# FTPSC.net
KiCad netlist of a schematic drawn in EAGLE
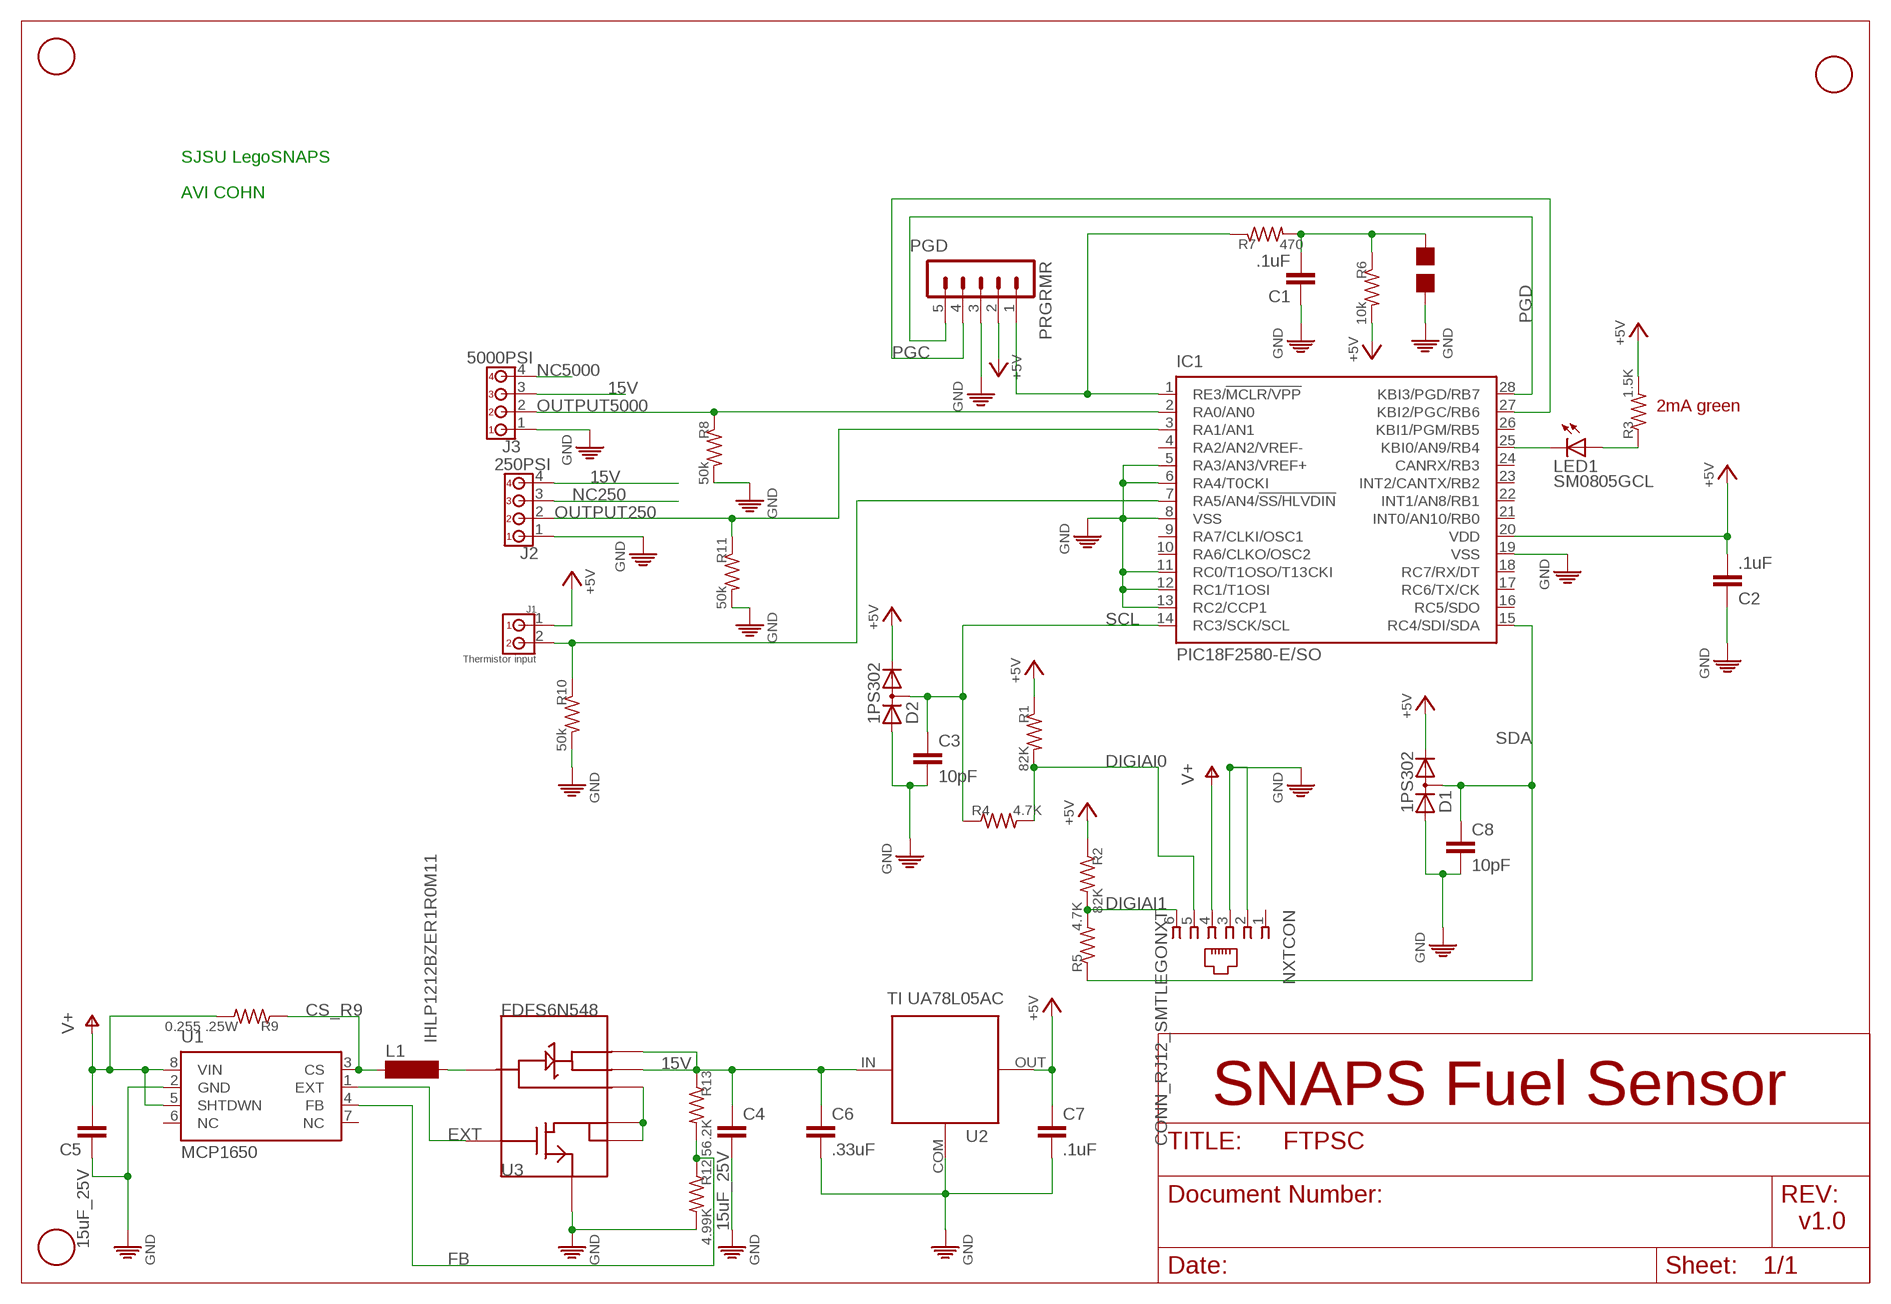
[diagram p0: schematic, sheet 1]

(export (version "E")
  (design (tool "Eeschema 10.0.6"))
  (components
    (comp (ref "C1")
      (value ".1uF")
      (footprint "eagle-import:RCL_C0805")
      (libsource (lib "eagle-import") (part "PASSIVE_CAP_NON-POLC0805"))
    )
    (comp (ref "C2")
      (value ".1uF")
      (footprint "eagle-import:RCL_C0805")
      (libsource (lib "eagle-import") (part "PASSIVE_CAP_NON-POLC0805"))
    )
    (comp (ref "C3")
      (value "10pF")
      (footprint "eagle-import:RCL_C0805")
      (libsource (lib "eagle-import") (part "PASSIVE_CAP_NON-POLC0805"))
    )
    (comp (ref "C4")
      (value "15uF_25V")
      (footprint "eagle-import:RCL_C0805")
      (libsource (lib "eagle-import") (part "PASSIVE_CAP_NON-POLC0805"))
    )
    (comp (ref "C5")
      (value "15uF_25V")
      (footprint "eagle-import:RCL_C0805")
      (libsource (lib "eagle-import") (part "PASSIVE_CAP_NON-POLC0805"))
    )
    (comp (ref "C6")
      (value ".33uF")
      (footprint "eagle-import:RCL_C0805")
      (libsource (lib "eagle-import") (part "PASSIVE_CAP_NON-POLC0805"))
    )
    (comp (ref "C7")
      (value ".1uF")
      (footprint "eagle-import:RCL_C0805")
      (libsource (lib "eagle-import") (part "PASSIVE_CAP_NON-POLC0805"))
    )
    (comp (ref "C8")
      (value "10pF")
      (footprint "eagle-import:RCL_C0805")
      (libsource (lib "eagle-import") (part "PASSIVE_CAP_NON-POLC0805"))
    )
    (comp (ref "D1")
      (value "1PS302")
      (footprint "eagle-import:SC70-3-R")
      (libsource (lib "eagle-import") (part "DIOD_DBL_SERIESSOT323"))
    )
    (comp (ref "D2")
      (value "1PS302")
      (footprint "eagle-import:SC70-3-R")
      (libsource (lib "eagle-import") (part "DIOD_DBL_SERIESSOT323"))
    )
    (comp (ref "IC1")
      (value "PIC18F2580-E/SO")
      (footprint "eagle-import:SO28W")
      (fields (field (name "MF") "MICROCHIP") (field (name "MPN") "PIC18F2580-I/SO"))
      (libsource (lib "eagle-import") (part "PIC18F280-E/SO5"))
    )
    (comp (ref "J1")
      (value "Thermistor input")
      (footprint "eagle-import:CON-MOLEX_22-23-2021")
      (libsource (lib "eagle-import") (part "CONN_KK_2-PIN"))
    )
    (comp (ref "J2")
      (value "250PSI")
      (footprint "eagle-import:CON-MOLEX_22-23-2041")
      (libsource (lib "eagle-import") (part "CONN_KK_4-PIN"))
    )
    (comp (ref "J3")
      (value "5000PSI")
      (footprint "eagle-import:CON-MOLEX_22-23-2041")
      (libsource (lib "eagle-import") (part "CONN_KK_4-PIN"))
    )
    (comp (ref "L1")
      (value "IHLP1212BZER1R0M11")
      (footprint "eagle-import:MS42")
      (libsource (lib "eagle-import") (part "MS42"))
    )
    (comp (ref "LED1")
      (value "SM0805GCL")
      (footprint "eagle-import:D0805")
      (libsource (lib "eagle-import") (part "LEDD0805"))
    )
    (comp (ref "NXTCON")
      (value "CONN_RJ12_SMTLEGONXT")
      (footprint "eagle-import:NXTCONN")
      (libsource (lib "eagle-import") (part "CONN_RJ12_SMTLEGONXT"))
    )
    (comp (ref "PRGRMR")
      (value "CONN_5-PIN")
      (footprint "eagle-import:CONN_5-PIN")
      (libsource (lib "eagle-import") (part "CONN_5-PIN"))
    )
    (comp (ref "R1")
      (value "82K")
      (footprint "eagle-import:RCL_M0805")
      (libsource (lib "eagle-import") (part "PASSIVE_RESISTORM0805"))
    )
    (comp (ref "R2")
      (value "82K")
      (footprint "eagle-import:RCL_M0805")
      (libsource (lib "eagle-import") (part "PASSIVE_RESISTORM0805"))
    )
    (comp (ref "R3")
      (value "1.5K")
      (footprint "eagle-import:RCL_M0805")
      (libsource (lib "eagle-import") (part "PASSIVE_RESISTORM0805"))
    )
    (comp (ref "R4")
      (value "4.7K")
      (footprint "eagle-import:RCL_M0805")
      (libsource (lib "eagle-import") (part "PASSIVE_RESISTORM0805"))
    )
    (comp (ref "R5")
      (value "4.7K")
      (footprint "eagle-import:RCL_M0805")
      (libsource (lib "eagle-import") (part "PASSIVE_RESISTORM0805"))
    )
    (comp (ref "R6")
      (value "10k")
      (footprint "eagle-import:RCL_M0805")
      (libsource (lib "eagle-import") (part "PASSIVE_RESISTORM0805"))
    )
    (comp (ref "R7")
      (value "470")
      (footprint "eagle-import:RCL_M0805")
      (libsource (lib "eagle-import") (part "PASSIVE_RESISTORM0805"))
    )
    (comp (ref "R8")
      (value "50k")
      (footprint "eagle-import:RCL_M0805")
      (libsource (lib "eagle-import") (part "PASSIVE_RESISTORM0805"))
    )
    (comp (ref "R9")
      (value "0.255 .25W")
      (footprint "eagle-import:RCL_M0805")
      (libsource (lib "eagle-import") (part "PASSIVE_RESISTORM0805"))
    )
    (comp (ref "R10")
      (value "50k")
      (footprint "eagle-import:RCL_M0805")
      (libsource (lib "eagle-import") (part "PASSIVE_RESISTORM0805"))
    )
    (comp (ref "R11")
      (value "50k")
      (footprint "eagle-import:RCL_M0805")
      (libsource (lib "eagle-import") (part "PASSIVE_RESISTORM0805"))
    )
    (comp (ref "R12")
      (value "4.99K")
      (footprint "eagle-import:RCL_M0805")
      (libsource (lib "eagle-import") (part "PASSIVE_RESISTORM0805"))
    )
    (comp (ref "R13")
      (value "56.2K")
      (footprint "eagle-import:RCL_M0805")
      (libsource (lib "eagle-import") (part "PASSIVE_RESISTORM0805"))
    )
    (comp (ref "T1")
      (value "PAD-PAIR")
      (footprint "eagle-import:P0805")
      (libsource (lib "eagle-import") (part "PAD-PAIR"))
    )
    (comp (ref "U$1")
      (value "FIDUCIAL")
      (footprint "eagle-import:FIDUCIAL_1MM")
      (libsource (lib "eagle-import") (part "FIDUCIAL"))
    )
    (comp (ref "U$2")
      (value "FIDUCIAL")
      (footprint "eagle-import:FIDUCIAL_1MM")
      (libsource (lib "eagle-import") (part "FIDUCIAL"))
    )
    (comp (ref "U$3")
      (value "FIDUCIAL")
      (footprint "eagle-import:FIDUCIAL_1MM")
      (libsource (lib "eagle-import") (part "FIDUCIAL"))
    )
    (comp (ref "U1")
      (value "MCP1650")
      (footprint "eagle-import:SOP-08")
      (fields (field (name "MF") "TEXAS INSTRUMENT CONNECTORS") (field (name "MPN") "TPS77301DGK"))
      (libsource (lib "eagle-import") (part "MCP165001"))
    )
    (comp (ref "U2")
      (value "TI UA78L05AC")
      (footprint "eagle-import:SOT-89")
      (libsource (lib "eagle-import") (part "VREG_3PINSOT89"))
    )
    (comp (ref "U3")
      (value "FDFS6N548")
      (footprint "eagle-import:SO8")
      (libsource (lib "eagle-import") (part "MOSFET/SCOTTKY"))
    )
  )
  (nets
    (net (code "1") (name "+5V") (class "Default")
      (node (ref "C2") (pin "2") (pinfunction "2_2") (pintype "passive"))
      (node (ref "C7") (pin "1") (pinfunction "1_1") (pintype "passive"))
      (node (ref "D1") (pin "2") (pinfunction "C_2") (pintype "passive"))
      (node (ref "D2") (pin "2") (pinfunction "C_2") (pintype "passive"))
      (node (ref "IC1") (pin "20") (pinfunction "VDD_20") (pintype "power_in"))
      (node (ref "J1") (pin "1") (pinfunction "1_1") (pintype "passive"))
      (node (ref "PRGRMR") (pin "2") (pinfunction "2_2") (pintype "passive"))
      (node (ref "R1") (pin "1") (pinfunction "1_1") (pintype "passive"))
      (node (ref "R2") (pin "1") (pinfunction "1_1") (pintype "passive"))
      (node (ref "R3") (pin "2") (pinfunction "2_2") (pintype "passive"))
      (node (ref "R6") (pin "2") (pinfunction "2_2") (pintype "passive"))
      (node (ref "U2") (pin "OUT") (pinfunction "OUT_OUT") (pintype "passive"))
    )
    (net (code "2") (name "/15V") (class "Default")
      (node (ref "C4") (pin "1") (pinfunction "1_1") (pintype "passive"))
      (node (ref "C6") (pin "1") (pinfunction "1_1") (pintype "passive"))
      (node (ref "J2") (pin "4") (pinfunction "4_4") (pintype "passive"))
      (node (ref "J3") (pin "3") (pinfunction "3_3") (pintype "passive"))
      (node (ref "R13") (pin "1") (pinfunction "1_1") (pintype "passive"))
      (node (ref "U2") (pin "IN") (pinfunction "IN_IN") (pintype "passive"))
      (node (ref "U3") (pin "7") (pinfunction "C_7") (pintype "passive"))
      (node (ref "U3") (pin "8") (pinfunction "C_8") (pintype "passive"))
    )
    (net (code "3") (name "/CS_R9") (class "Default")
      (node (ref "L1") (pin "1") (pinfunction "1_1") (pintype "passive"))
      (node (ref "R9") (pin "1") (pinfunction "1_1") (pintype "passive"))
      (node (ref "U1") (pin "3") (pinfunction "CS_3") (pintype "input"))
    )
    (net (code "4") (name "/DIGIAI0") (class "Default")
      (node (ref "NXTCON") (pin "5") (pinfunction "5_5") (pintype "passive"))
      (node (ref "R1") (pin "2") (pinfunction "2_2") (pintype "passive"))
      (node (ref "R4") (pin "2") (pinfunction "2_2") (pintype "passive"))
    )
    (net (code "5") (name "/DIGIAI1") (class "Default")
      (node (ref "NXTCON") (pin "6") (pinfunction "6_6") (pintype "passive"))
      (node (ref "R2") (pin "2") (pinfunction "2_2") (pintype "passive"))
      (node (ref "R5") (pin "2") (pinfunction "2_2") (pintype "passive"))
    )
    (net (code "6") (name "/EXT") (class "Default")
      (node (ref "U1") (pin "1") (pinfunction "EXT_1") (pintype "input"))
      (node (ref "U3") (pin "4") (pinfunction "G_4") (pintype "passive"))
    )
    (net (code "7") (name "/FB") (class "Default")
      (node (ref "R12") (pin "1") (pinfunction "1_1") (pintype "passive"))
      (node (ref "R13") (pin "2") (pinfunction "2_2") (pintype "passive"))
      (node (ref "U1") (pin "4") (pinfunction "FB_4") (pintype "passive"))
    )
    (net (code "8") (name "/NC250") (class "Default")
      (node (ref "J2") (pin "3") (pinfunction "3_3") (pintype "passive"))
    )
    (net (code "9") (name "/NC5000") (class "Default")
      (node (ref "J3") (pin "4") (pinfunction "4_4") (pintype "passive"))
    )
    (net (code "10") (name "/OUTPUT250") (class "Default")
      (node (ref "IC1") (pin "3") (pinfunction "RA1/AN1_3") (pintype "bidirectional"))
      (node (ref "J2") (pin "2") (pinfunction "2_2") (pintype "passive"))
      (node (ref "R11") (pin "1") (pinfunction "1_1") (pintype "passive"))
    )
    (net (code "11") (name "/OUTPUT5000") (class "Default")
      (node (ref "IC1") (pin "2") (pinfunction "RA0/AN0_2") (pintype "bidirectional"))
      (node (ref "J3") (pin "2") (pinfunction "2_2") (pintype "passive"))
      (node (ref "R8") (pin "1") (pinfunction "1_1") (pintype "passive"))
    )
    (net (code "12") (name "/PGC") (class "Default")
      (node (ref "IC1") (pin "27") (pinfunction "KBI2/PGC/RB6_27") (pintype "bidirectional"))
      (node (ref "PRGRMR") (pin "4") (pinfunction "4_4") (pintype "passive"))
    )
    (net (code "13") (name "/PGD") (class "Default")
      (node (ref "IC1") (pin "28") (pinfunction "KBI3/PGD/RB7_28") (pintype "bidirectional"))
      (node (ref "PRGRMR") (pin "5") (pinfunction "5_5") (pintype "passive"))
    )
    (net (code "14") (name "/SCL") (class "Default")
      (node (ref "C3") (pin "1") (pinfunction "1_1") (pintype "passive"))
      (node (ref "D2") (pin "3") (pinfunction "AC_3") (pintype "passive"))
      (node (ref "IC1") (pin "14") (pinfunction "RC3/SCK/SCL_14") (pintype "bidirectional"))
      (node (ref "R4") (pin "1") (pinfunction "1_1") (pintype "passive"))
    )
    (net (code "15") (name "/SDA") (class "Default")
      (node (ref "C8") (pin "1") (pinfunction "1_1") (pintype "passive"))
      (node (ref "D1") (pin "3") (pinfunction "AC_3") (pintype "passive"))
      (node (ref "IC1") (pin "15") (pinfunction "RC4/SDI/SDA_15") (pintype "bidirectional"))
      (node (ref "R5") (pin "1") (pinfunction "1_1") (pintype "passive"))
    )
    (net (code "16") (name "GND") (class "Default")
      (node (ref "C1") (pin "1") (pinfunction "1_1") (pintype "passive"))
      (node (ref "C2") (pin "1") (pinfunction "1_1") (pintype "passive"))
      (node (ref "C3") (pin "2") (pinfunction "2_2") (pintype "passive"))
      (node (ref "C4") (pin "2") (pinfunction "2_2") (pintype "passive"))
      (node (ref "C5") (pin "1") (pinfunction "1_1") (pintype "passive"))
      (node (ref "C6") (pin "2") (pinfunction "2_2") (pintype "passive"))
      (node (ref "C7") (pin "2") (pinfunction "2_2") (pintype "passive"))
      (node (ref "C8") (pin "2") (pinfunction "2_2") (pintype "passive"))
      (node (ref "D1") (pin "1") (pinfunction "A_1") (pintype "passive"))
      (node (ref "D2") (pin "1") (pinfunction "A_1") (pintype "passive"))
      (node (ref "IC1") (pin "11") (pinfunction "RC0/T1OSO/T13CKI_11") (pintype "bidirectional"))
      (node (ref "IC1") (pin "12") (pinfunction "RC1/T1OSI_12") (pintype "bidirectional"))
      (node (ref "IC1") (pin "13") (pinfunction "RC2/CCP1_13") (pintype "bidirectional"))
      (node (ref "IC1") (pin "19") (pinfunction "VSS_19") (pintype "power_in"))
      (node (ref "IC1") (pin "5") (pinfunction "RA3/AN3/VREF+_5") (pintype "bidirectional"))
      (node (ref "IC1") (pin "6") (pinfunction "RA4/T0CKI_6") (pintype "bidirectional"))
      (node (ref "IC1") (pin "8") (pinfunction "VSS_8") (pintype "power_in"))
      (node (ref "J2") (pin "1") (pinfunction "1_1") (pintype "passive"))
      (node (ref "J3") (pin "1") (pinfunction "1_1") (pintype "passive"))
      (node (ref "NXTCON") (pin "2") (pinfunction "2_2") (pintype "passive"))
      (node (ref "NXTCON") (pin "3") (pinfunction "3_3") (pintype "passive"))
      (node (ref "PRGRMR") (pin "3") (pinfunction "3_3") (pintype "passive"))
      (node (ref "R10") (pin "2") (pinfunction "2_2") (pintype "passive"))
      (node (ref "R11") (pin "2") (pinfunction "2_2") (pintype "passive"))
      (node (ref "R12") (pin "2") (pinfunction "2_2") (pintype "passive"))
      (node (ref "R8") (pin "2") (pinfunction "2_2") (pintype "passive"))
      (node (ref "T1") (pin "1") (pinfunction "P$1_1") (pintype "passive"))
      (node (ref "U1") (pin "2") (pinfunction "GND_2") (pintype "input"))
      (node (ref "U2") (pin "COM") (pinfunction "COM_COM") (pintype "passive"))
      (node (ref "U3") (pin "3") (pinfunction "S_3") (pintype "passive"))
    )
    (net (code "17") (name "Net-(IC1-KBI0{slash}AN9{slash}RB4)") (class "Default")
      (node (ref "IC1") (pin "25") (pinfunction "KBI0/AN9/RB4_25") (pintype "bidirectional"))
      (node (ref "LED1") (pin "C") (pinfunction "C_C") (pintype "passive"))
    )
    (net (code "18") (name "Net-(IC1-RA5{slash}AN4{slash}~{SS{slash}HLVDIN})") (class "Default")
      (node (ref "IC1") (pin "7") (pinfunction "RA5/AN4/~{SS/HLVDIN}_7") (pintype "bidirectional"))
      (node (ref "J1") (pin "2") (pinfunction "2_2") (pintype "passive"))
      (node (ref "R10") (pin "1") (pinfunction "1_1") (pintype "passive"))
    )
    (net (code "19") (name "Net-(IC1-RE3{slash}~{MCLR{slash}VPP})") (class "Default")
      (node (ref "IC1") (pin "1") (pinfunction "RE3/~{MCLR/VPP}_1") (pintype "input"))
      (node (ref "PRGRMR") (pin "1") (pinfunction "1_1") (pintype "passive"))
      (node (ref "R7") (pin "1") (pinfunction "1_1") (pintype "passive"))
    )
    (net (code "20") (name "Net-(L1-Pad2)") (class "Default")
      (node (ref "L1") (pin "2") (pinfunction "2_2") (pintype "passive"))
      (node (ref "U3") (pin "1") (pinfunction "A_1") (pintype "passive"))
    )
    (net (code "21") (name "Net-(LED1-PadA)") (class "Default")
      (node (ref "LED1") (pin "A") (pinfunction "A_A") (pintype "passive"))
      (node (ref "R3") (pin "1") (pinfunction "1_1") (pintype "passive"))
    )
    (net (code "22") (name "Net-(T1-P$2)") (class "Default")
      (node (ref "C1") (pin "2") (pinfunction "2_2") (pintype "passive"))
      (node (ref "R6") (pin "1") (pinfunction "1_1") (pintype "passive"))
      (node (ref "R7") (pin "2") (pinfunction "2_2") (pintype "passive"))
      (node (ref "T1") (pin "2") (pinfunction "P$2_2") (pintype "passive"))
    )
    (net (code "23") (name "Net-(U3-A-Pad2)") (class "Default")
      (node (ref "U3") (pin "2") (pinfunction "A_2") (pintype "passive"))
      (node (ref "U3") (pin "5") (pinfunction "D_5") (pintype "passive"))
      (node (ref "U3") (pin "6") (pinfunction "D_6") (pintype "passive"))
    )
    (net (code "24") (name "V+") (class "Default")
      (node (ref "C5") (pin "2") (pinfunction "2_2") (pintype "passive"))
      (node (ref "NXTCON") (pin "4") (pinfunction "4_4") (pintype "passive"))
      (node (ref "R9") (pin "2") (pinfunction "2_2") (pintype "passive"))
      (node (ref "U1") (pin "5") (pinfunction "SHTDWN_5") (pintype "input"))
      (node (ref "U1") (pin "8") (pinfunction "VIN_8") (pintype "passive"))
    )
    (net (code "25") (name "unconnected-(IC1-CANRX{slash}RB3-Pad24)") (class "Default")
      (node (ref "IC1") (pin "24") (pinfunction "CANRX/RB3_24") (pintype "bidirectional"))
    )
    (net (code "26") (name "unconnected-(IC1-INT0{slash}AN10{slash}RB0-Pad21)") (class "Default")
      (node (ref "IC1") (pin "21") (pinfunction "INT0/AN10/RB0_21") (pintype "bidirectional"))
    )
    (net (code "27") (name "unconnected-(IC1-INT1{slash}AN8{slash}RB1-Pad22)") (class "Default")
      (node (ref "IC1") (pin "22") (pinfunction "INT1/AN8/RB1_22") (pintype "bidirectional"))
    )
    (net (code "28") (name "unconnected-(IC1-INT2{slash}CANTX{slash}RB2-Pad23)") (class "Default")
      (node (ref "IC1") (pin "23") (pinfunction "INT2/CANTX/RB2_23") (pintype "bidirectional"))
    )
    (net (code "29") (name "unconnected-(IC1-KBI1{slash}PGM{slash}RB5-Pad26)") (class "Default")
      (node (ref "IC1") (pin "26") (pinfunction "KBI1/PGM/RB5_26") (pintype "bidirectional"))
    )
    (net (code "30") (name "unconnected-(IC1-RA2{slash}AN2{slash}VREF--Pad4)") (class "Default")
      (node (ref "IC1") (pin "4") (pinfunction "RA2/AN2/VREF-_4") (pintype "bidirectional"))
    )
    (net (code "31") (name "unconnected-(IC1-RA6{slash}CLKO{slash}OSC2-Pad10)") (class "Default")
      (node (ref "IC1") (pin "10") (pinfunction "RA6/CLKO/OSC2_10") (pintype "output"))
    )
    (net (code "32") (name "unconnected-(IC1-RA7{slash}CLKI{slash}OSC1-Pad9)") (class "Default")
      (node (ref "IC1") (pin "9") (pinfunction "RA7/CLKI/OSC1_9") (pintype "bidirectional"))
    )
    (net (code "33") (name "unconnected-(IC1-RC5{slash}SDO-Pad16)") (class "Default")
      (node (ref "IC1") (pin "16") (pinfunction "RC5/SDO_16") (pintype "bidirectional"))
    )
    (net (code "34") (name "unconnected-(IC1-RC6{slash}TX{slash}CK-Pad17)") (class "Default")
      (node (ref "IC1") (pin "17") (pinfunction "RC6/TX/CK_17") (pintype "bidirectional"))
    )
    (net (code "35") (name "unconnected-(IC1-RC7{slash}RX{slash}DT-Pad18)") (class "Default")
      (node (ref "IC1") (pin "18") (pinfunction "RC7/RX/DT_18") (pintype "bidirectional"))
    )
    (net (code "36") (name "unconnected-(NXTCON-Pad1)") (class "Default")
      (node (ref "NXTCON") (pin "1") (pinfunction "1_1") (pintype "passive"))
    )
    (net (code "37") (name "unconnected-(U1-NC-Pad6)") (class "Default")
      (node (ref "U1") (pin "6") (pinfunction "NC_6") (pintype "input"))
    )
    (net (code "38") (name "unconnected-(U1-NC-Pad7)") (class "Default")
      (node (ref "U1") (pin "7") (pinfunction "NC_7") (pintype "output"))
    )
  )
)
